# mm_legend_v2.net
KiCad netlist of a schematic drawn in EAGLE
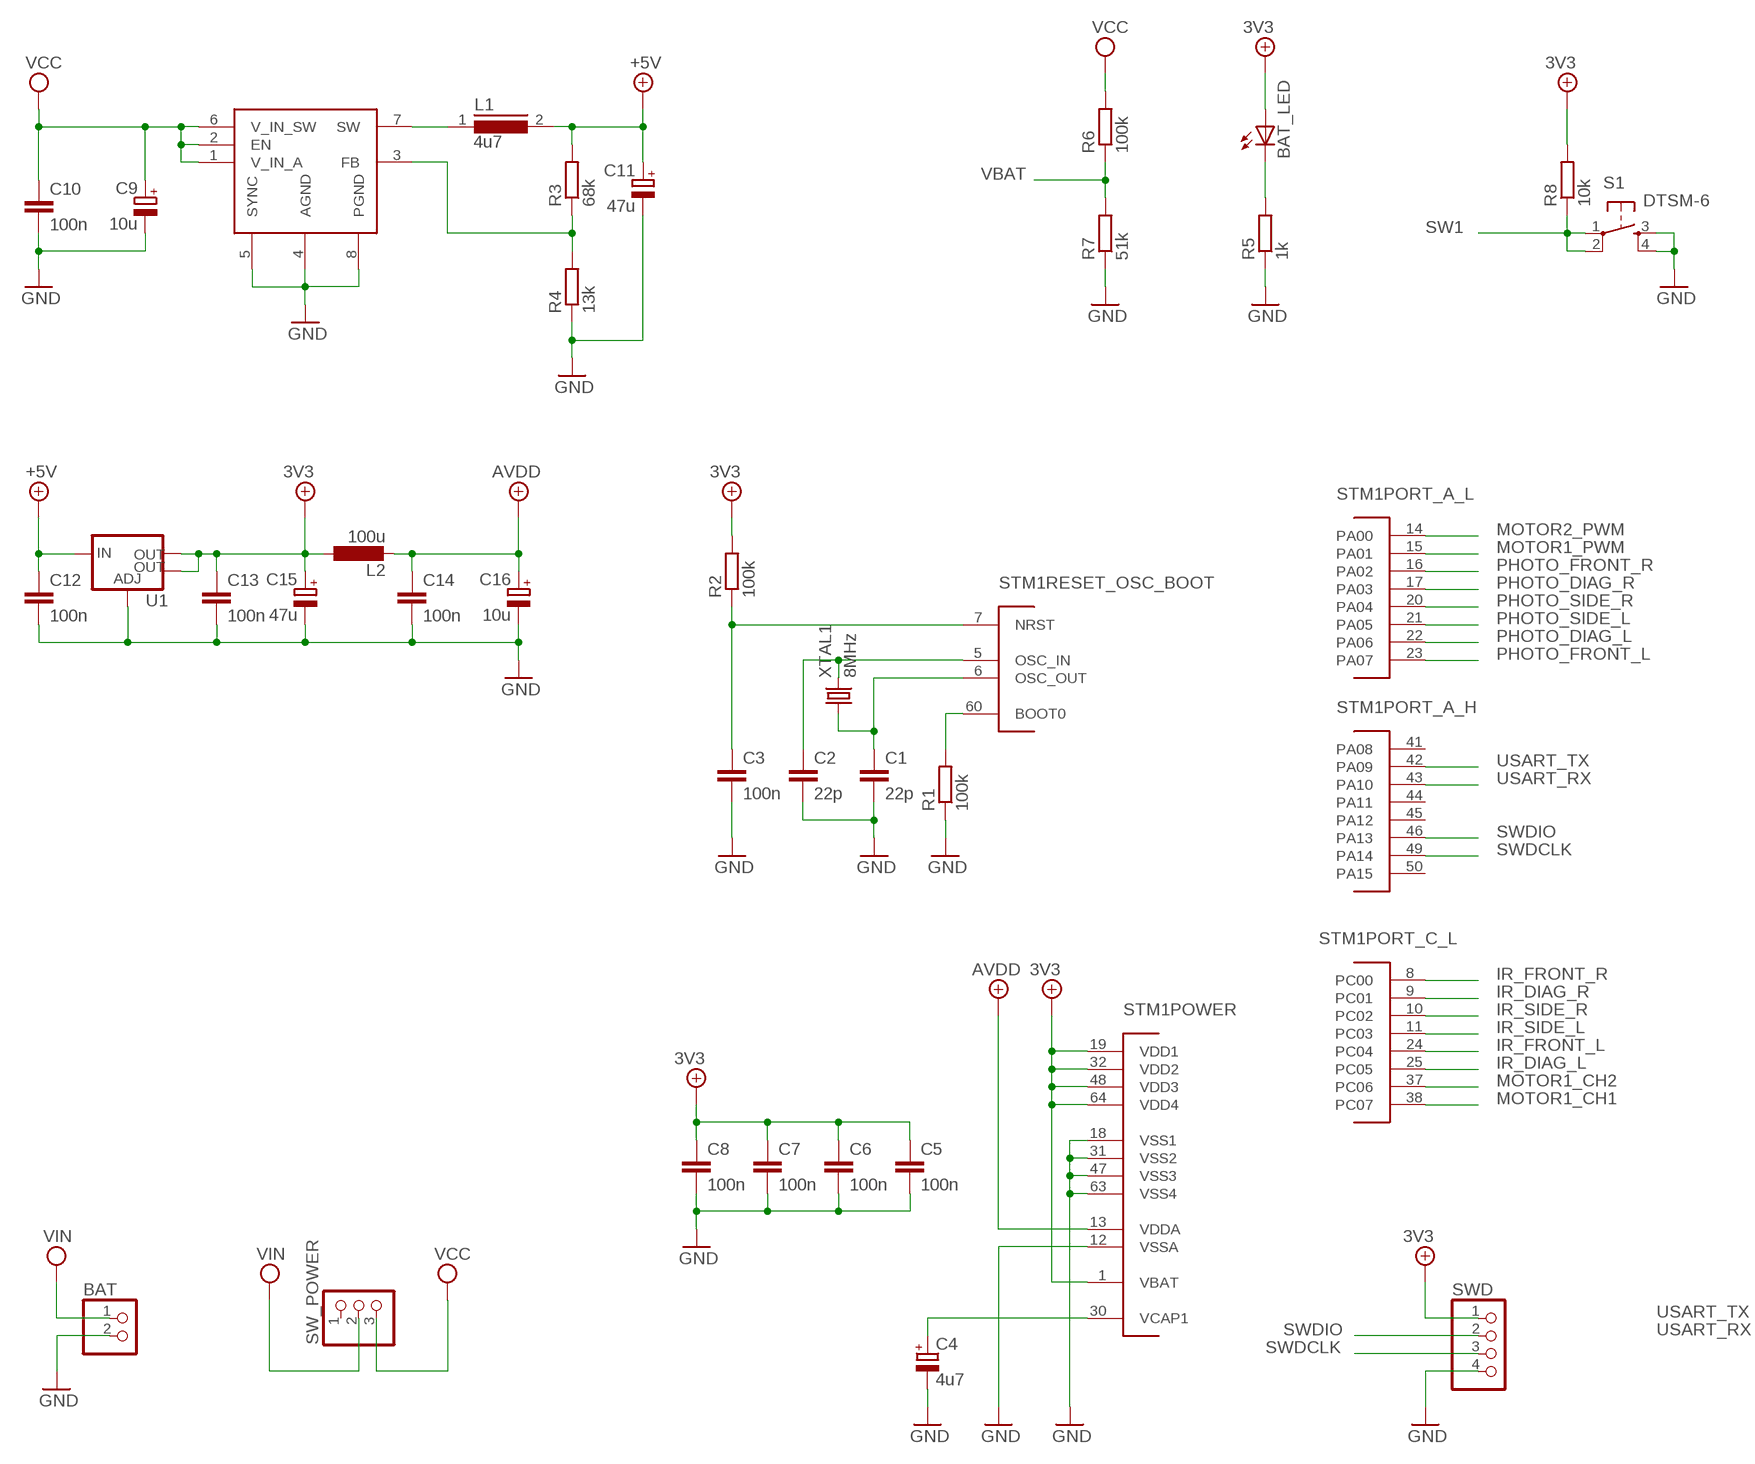
[diagram p0: schematic, sheet 1, part 1 of 2]
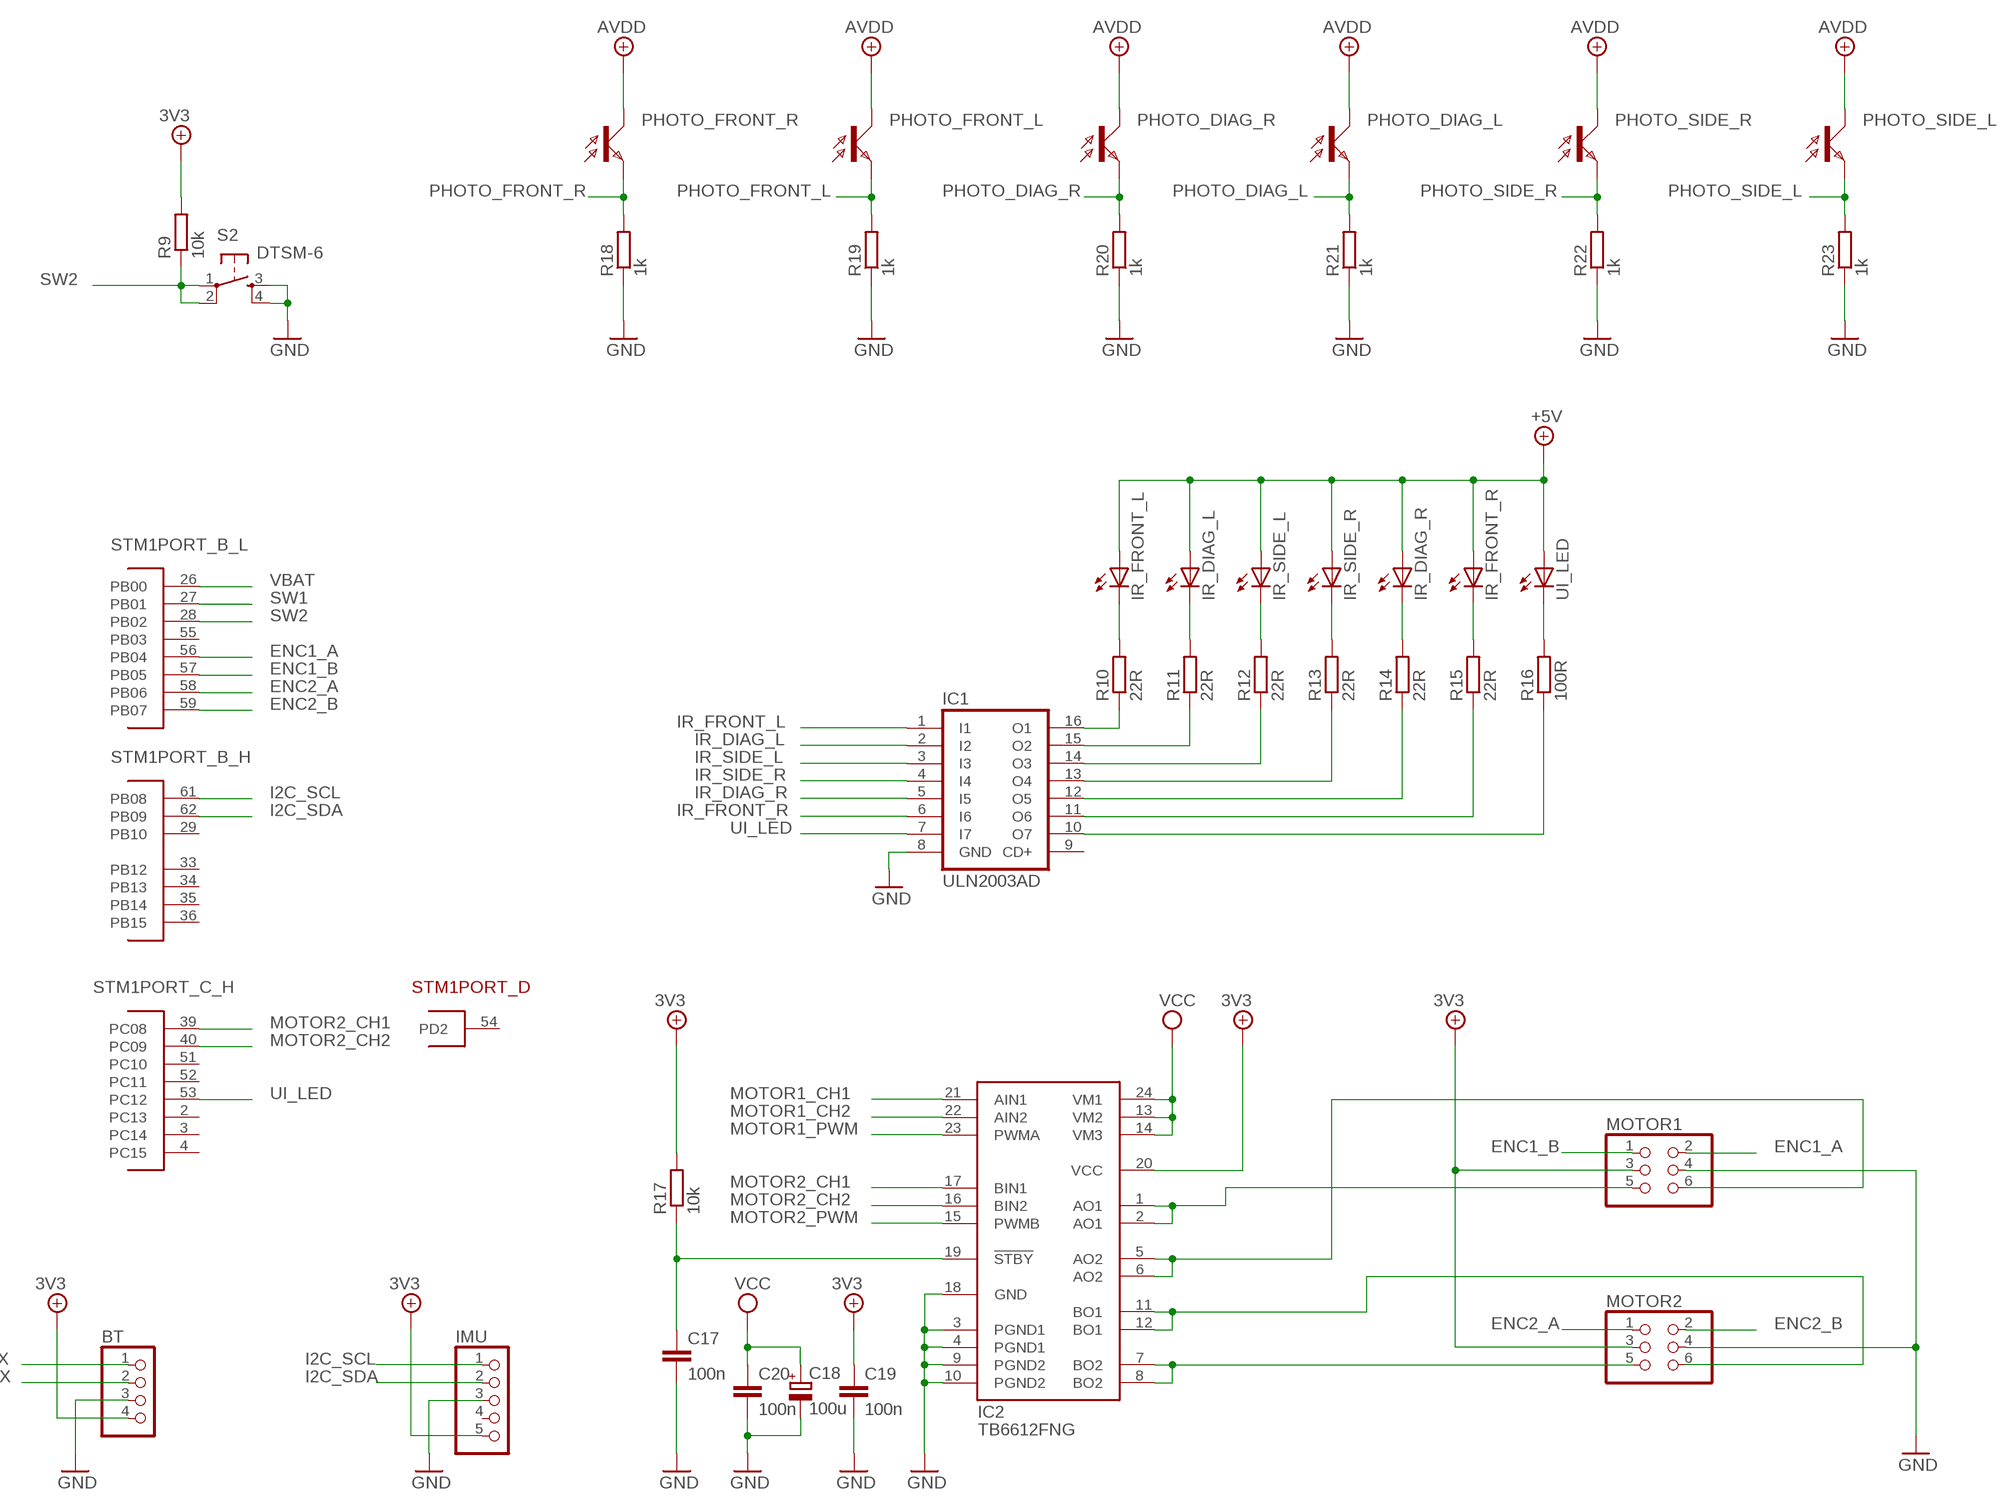
[diagram p1: schematic, sheet 1, part 2 of 2]

(export (version "E")
  (design (tool "Eeschema 10.0.6"))
  (components
    (comp (ref "BAT")
      (value "PINHD-1X2")
      (footprint "eagle-import:1X02")
      (libsource (lib "eagle-import") (part "PINHD-1X2"))
    )
    (comp (ref "BAT_LED")
      (value "LEDCHIP-LED0805")
      (footprint "eagle-import:CHIP-LED0805")
      (libsource (lib "eagle-import") (part "LEDCHIP-LED0805"))
    )
    (comp (ref "BT")
      (value "PINHD-1X4")
      (footprint "eagle-import:1X04")
      (libsource (lib "eagle-import") (part "PINHD-1X4"))
    )
    (comp (ref "C1")
      (value "22p")
      (footprint "eagle-import:C0805K")
      (libsource (lib "eagle-import") (part "C-EUC0805K"))
    )
    (comp (ref "C2")
      (value "22p")
      (footprint "eagle-import:C0805K")
      (libsource (lib "eagle-import") (part "C-EUC0805K"))
    )
    (comp (ref "C3")
      (value "100n")
      (footprint "eagle-import:C0805K")
      (libsource (lib "eagle-import") (part "C-EUC0805K"))
    )
    (comp (ref "C4")
      (value "4u7")
      (footprint "eagle-import:A_3216-18R")
      (libsource (lib "eagle-import") (part "CPOL-EUA/3216-18R"))
    )
    (comp (ref "C5")
      (value "100n")
      (footprint "eagle-import:C0805K")
      (libsource (lib "eagle-import") (part "C-EUC0805K"))
    )
    (comp (ref "C6")
      (value "100n")
      (footprint "eagle-import:C0805K")
      (libsource (lib "eagle-import") (part "C-EUC0805K"))
    )
    (comp (ref "C7")
      (value "100n")
      (footprint "eagle-import:C0805K")
      (libsource (lib "eagle-import") (part "C-EUC0805K"))
    )
    (comp (ref "C8")
      (value "100n")
      (footprint "eagle-import:C0805K")
      (libsource (lib "eagle-import") (part "C-EUC0805K"))
    )
    (comp (ref "C9")
      (value "10u")
      (footprint "eagle-import:A_3216-18R")
      (libsource (lib "eagle-import") (part "CPOL-EUA/3216-18R"))
    )
    (comp (ref "C10")
      (value "100n")
      (footprint "eagle-import:C0805K")
      (libsource (lib "eagle-import") (part "C-EUC0805K"))
    )
    (comp (ref "C11")
      (value "47u")
      (footprint "eagle-import:B_3528-21W")
      (libsource (lib "eagle-import") (part "CPOL-EUB/3528-21W"))
    )
    (comp (ref "C12")
      (value "100n")
      (footprint "eagle-import:C0805K")
      (libsource (lib "eagle-import") (part "C-EUC0805K"))
    )
    (comp (ref "C13")
      (value "100n")
      (footprint "eagle-import:C0805K")
      (libsource (lib "eagle-import") (part "C-EUC0805K"))
    )
    (comp (ref "C14")
      (value "100n")
      (footprint "eagle-import:C0805K")
      (libsource (lib "eagle-import") (part "C-EUC0805K"))
    )
    (comp (ref "C15")
      (value "47u")
      (footprint "eagle-import:B_3528-21W")
      (libsource (lib "eagle-import") (part "CPOL-EUB/3528-21W"))
    )
    (comp (ref "C16")
      (value "10u")
      (footprint "eagle-import:A_3216-18R")
      (libsource (lib "eagle-import") (part "CPOL-EUA/3216-18R"))
    )
    (comp (ref "C17")
      (value "100n")
      (footprint "eagle-import:C0805K")
      (libsource (lib "eagle-import") (part "C-EUC0805K"))
    )
    (comp (ref "C18")
      (value "100u")
      (footprint "eagle-import:C_6032-28R")
      (libsource (lib "eagle-import") (part "CPOL-EUC/6032-28R"))
    )
    (comp (ref "C19")
      (value "100n")
      (footprint "eagle-import:C0805K")
      (libsource (lib "eagle-import") (part "C-EUC0805K"))
    )
    (comp (ref "C20")
      (value "100n")
      (footprint "eagle-import:C0805K")
      (libsource (lib "eagle-import") (part "C-EUC0805K"))
    )
    (comp (ref "IC1")
      (value "ULN2003AD")
      (footprint "eagle-import:SO16")
      (libsource (lib "eagle-import") (part "ULN2003AD"))
    )
    (comp (ref "IC2")
      (value "TB6612FNG")
      (footprint "eagle-import:SSOP24")
      (libsource (lib "eagle-import") (part "TB6612FNG"))
    )
    (comp (ref "IMU")
      (value "PINHD-1X5")
      (footprint "eagle-import:1X05")
      (libsource (lib "eagle-import") (part "PINHD-1X5"))
    )
    (comp (ref "IR_DIAG_L")
      (value "LED5MM")
      (footprint "eagle-import:LED5MM")
      (libsource (lib "eagle-import") (part "LED5MM"))
    )
    (comp (ref "IR_DIAG_R")
      (value "LED5MM")
      (footprint "eagle-import:LED5MM")
      (libsource (lib "eagle-import") (part "LED5MM"))
    )
    (comp (ref "IR_FRONT_L")
      (value "LED5MM")
      (footprint "eagle-import:LED5MM")
      (libsource (lib "eagle-import") (part "LED5MM"))
    )
    (comp (ref "IR_FRONT_R")
      (value "LED5MM")
      (footprint "eagle-import:LED5MM")
      (libsource (lib "eagle-import") (part "LED5MM"))
    )
    (comp (ref "IR_SIDE_L")
      (value "LED5MM")
      (footprint "eagle-import:LED5MM")
      (libsource (lib "eagle-import") (part "LED5MM"))
    )
    (comp (ref "IR_SIDE_R")
      (value "LED5MM")
      (footprint "eagle-import:LED5MM")
      (libsource (lib "eagle-import") (part "LED5MM"))
    )
    (comp (ref "L1")
      (value "4u7")
      (footprint "eagle-import:DR74")
      (libsource (lib "eagle-import") (part "DR74"))
    )
    (comp (ref "L2")
      (value "100u")
      (footprint "eagle-import:L1812")
      (libsource (lib "eagle-import") (part "L-EUL1812"))
    )
    (comp (ref "MOTOR1")
      (value "PINHD-2X3")
      (footprint "eagle-import:2X03")
      (libsource (lib "eagle-import") (part "PINHD-2X3"))
    )
    (comp (ref "MOTOR2")
      (value "PINHD-2X3")
      (footprint "eagle-import:2X03")
      (libsource (lib "eagle-import") (part "PINHD-2X3"))
    )
    (comp (ref "PHOTO_DIAG_L")
      (value "PHOTO_TRANSISTOR_5MM")
      (footprint "eagle-import:5MM")
      (libsource (lib "eagle-import") (part "PHOTO_TRANSISTOR_5MM"))
    )
    (comp (ref "PHOTO_DIAG_R")
      (value "PHOTO_TRANSISTOR_5MM")
      (footprint "eagle-import:5MM")
      (libsource (lib "eagle-import") (part "PHOTO_TRANSISTOR_5MM"))
    )
    (comp (ref "PHOTO_FRONT_L")
      (value "PHOTO_TRANSISTOR_5MM")
      (footprint "eagle-import:5MM")
      (libsource (lib "eagle-import") (part "PHOTO_TRANSISTOR_5MM"))
    )
    (comp (ref "PHOTO_FRONT_R")
      (value "PHOTO_TRANSISTOR_5MM")
      (footprint "eagle-import:5MM")
      (libsource (lib "eagle-import") (part "PHOTO_TRANSISTOR_5MM"))
    )
    (comp (ref "PHOTO_SIDE_L")
      (value "PHOTO_TRANSISTOR_5MM")
      (footprint "eagle-import:5MM")
      (libsource (lib "eagle-import") (part "PHOTO_TRANSISTOR_5MM"))
    )
    (comp (ref "PHOTO_SIDE_R")
      (value "PHOTO_TRANSISTOR_5MM")
      (footprint "eagle-import:5MM")
      (libsource (lib "eagle-import") (part "PHOTO_TRANSISTOR_5MM"))
    )
    (comp (ref "R1")
      (value "100k")
      (footprint "eagle-import:R0805W")
      (libsource (lib "eagle-import") (part "R-EU_R0805W"))
    )
    (comp (ref "R2")
      (value "100k")
      (footprint "eagle-import:R0805W")
      (libsource (lib "eagle-import") (part "R-EU_R0805W"))
    )
    (comp (ref "R3")
      (value "68k")
      (footprint "eagle-import:R0805W")
      (libsource (lib "eagle-import") (part "R-EU_R0805W"))
    )
    (comp (ref "R4")
      (value "13k")
      (footprint "eagle-import:R0805W")
      (libsource (lib "eagle-import") (part "R-EU_R0805W"))
    )
    (comp (ref "R5")
      (value "1k")
      (footprint "eagle-import:R0805W")
      (libsource (lib "eagle-import") (part "R-EU_R0805W"))
    )
    (comp (ref "R6")
      (value "100k")
      (footprint "eagle-import:R0805W")
      (libsource (lib "eagle-import") (part "R-EU_R0805W"))
    )
    (comp (ref "R7")
      (value "51k")
      (footprint "eagle-import:R0805W")
      (libsource (lib "eagle-import") (part "R-EU_R0805W"))
    )
    (comp (ref "R8")
      (value "10k")
      (footprint "eagle-import:R0805W")
      (libsource (lib "eagle-import") (part "R-EU_R0805W"))
    )
    (comp (ref "R9")
      (value "10k")
      (footprint "eagle-import:R0805W")
      (libsource (lib "eagle-import") (part "R-EU_R0805W"))
    )
    (comp (ref "R10")
      (value "22R")
      (footprint "eagle-import:R0805W")
      (libsource (lib "eagle-import") (part "R-EU_R0805W"))
    )
    (comp (ref "R11")
      (value "22R")
      (footprint "eagle-import:R0805W")
      (libsource (lib "eagle-import") (part "R-EU_R0805W"))
    )
    (comp (ref "R12")
      (value "22R")
      (footprint "eagle-import:R0805W")
      (libsource (lib "eagle-import") (part "R-EU_R0805W"))
    )
    (comp (ref "R13")
      (value "22R")
      (footprint "eagle-import:R0805W")
      (libsource (lib "eagle-import") (part "R-EU_R0805W"))
    )
    (comp (ref "R14")
      (value "22R")
      (footprint "eagle-import:R0805W")
      (libsource (lib "eagle-import") (part "R-EU_R0805W"))
    )
    (comp (ref "R15")
      (value "22R")
      (footprint "eagle-import:R0805W")
      (libsource (lib "eagle-import") (part "R-EU_R0805W"))
    )
    (comp (ref "R16")
      (value "100R")
      (footprint "eagle-import:R0805W")
      (libsource (lib "eagle-import") (part "R-EU_R0805W"))
    )
    (comp (ref "R17")
      (value "10k")
      (footprint "eagle-import:R0805W")
      (libsource (lib "eagle-import") (part "R-EU_R0805W"))
    )
    (comp (ref "R18")
      (value "1k")
      (footprint "eagle-import:R0805W")
      (libsource (lib "eagle-import") (part "R-EU_R0805W"))
    )
    (comp (ref "R19")
      (value "1k")
      (footprint "eagle-import:R0805W")
      (libsource (lib "eagle-import") (part "R-EU_R0805W"))
    )
    (comp (ref "R20")
      (value "1k")
      (footprint "eagle-import:R0805W")
      (libsource (lib "eagle-import") (part "R-EU_R0805W"))
    )
    (comp (ref "R21")
      (value "1k")
      (footprint "eagle-import:R0805W")
      (libsource (lib "eagle-import") (part "R-EU_R0805W"))
    )
    (comp (ref "R22")
      (value "1k")
      (footprint "eagle-import:R0805W")
      (libsource (lib "eagle-import") (part "R-EU_R0805W"))
    )
    (comp (ref "R23")
      (value "1k")
      (footprint "eagle-import:R0805W")
      (libsource (lib "eagle-import") (part "R-EU_R0805W"))
    )
    (comp (ref "S1")
      (value "DTSM-6")
      (footprint "eagle-import:DTSM-6")
      (libsource (lib "eagle-import") (part "DTSM-6"))
    )
    (comp (ref "S2")
      (value "DTSM-6")
      (footprint "eagle-import:DTSM-6")
      (libsource (lib "eagle-import") (part "DTSM-6"))
    )
    (comp (ref "STM1")
      (value "STM32F401RB")
      (footprint "eagle-import:LQFP64")
      (libsource (lib "eagle-import") (part "STM32F401RB"))
    )
    (comp (ref "SWD")
      (value "PINHD-1X4")
      (footprint "eagle-import:1X04")
      (libsource (lib "eagle-import") (part "PINHD-1X4"))
    )
    (comp (ref "SW_POWER")
      (value "PINHD-1X3")
      (footprint "eagle-import:1X03")
      (libsource (lib "eagle-import") (part "PINHD-1X3"))
    )
    (comp (ref "U$2")
      (value "ST1S10PHR")
      (footprint "eagle-import:SO8")
      (libsource (lib "eagle-import") (part "ST1S10PHR"))
    )
    (comp (ref "U1")
      (value "V_REG_LM1117SOT223")
      (footprint "eagle-import:SOT223")
      (libsource (lib "eagle-import") (part "V_REG_LM1117SOT223"))
    )
    (comp (ref "UI_LED")
      (value "LEDCHIP-LED0805")
      (footprint "eagle-import:CHIP-LED0805")
      (libsource (lib "eagle-import") (part "LEDCHIP-LED0805"))
    )
    (comp (ref "XTAL1")
      (value "8MHz")
      (footprint "eagle-import:SMD_50X32")
      (libsource (lib "eagle-import") (part "XTAL_SMD_50X32"))
    )
  )
  (nets
    (net (code "1") (name "+5V") (class "Default")
      (node (ref "C11") (pin "+") (pinfunction "+_+") (pintype "passive"))
      (node (ref "C12") (pin "1") (pinfunction "1_1") (pintype "passive"))
      (node (ref "IR_DIAG_L") (pin "A") (pinfunction "A_A") (pintype "passive"))
      (node (ref "IR_DIAG_R") (pin "A") (pinfunction "A_A") (pintype "passive"))
      (node (ref "IR_FRONT_L") (pin "A") (pinfunction "A_A") (pintype "passive"))
      (node (ref "IR_FRONT_R") (pin "A") (pinfunction "A_A") (pintype "passive"))
      (node (ref "IR_SIDE_L") (pin "A") (pinfunction "A_A") (pintype "passive"))
      (node (ref "IR_SIDE_R") (pin "A") (pinfunction "A_A") (pintype "passive"))
      (node (ref "L1") (pin "2") (pinfunction "2_2") (pintype "passive"))
      (node (ref "R3") (pin "2") (pinfunction "2_2") (pintype "passive"))
      (node (ref "U1") (pin "3") (pinfunction "IN_3") (pintype "input"))
      (node (ref "UI_LED") (pin "A") (pinfunction "A_A") (pintype "passive"))
    )
    (net (code "2") (name "/ENC1_A") (class "Default")
      (node (ref "MOTOR1") (pin "2") (pinfunction "2_2") (pintype "passive"))
      (node (ref "STM1") (pin "56") (pinfunction "PB04_56") (pintype "bidirectional"))
    )
    (net (code "3") (name "/ENC1_B") (class "Default")
      (node (ref "MOTOR1") (pin "1") (pinfunction "1_1") (pintype "passive"))
      (node (ref "STM1") (pin "57") (pinfunction "PB05_57") (pintype "bidirectional"))
    )
    (net (code "4") (name "/ENC2_A") (class "Default")
      (node (ref "MOTOR2") (pin "1") (pinfunction "1_1") (pintype "passive"))
      (node (ref "STM1") (pin "58") (pinfunction "PB06_58") (pintype "bidirectional"))
    )
    (net (code "5") (name "/ENC2_B") (class "Default")
      (node (ref "MOTOR2") (pin "2") (pinfunction "2_2") (pintype "passive"))
      (node (ref "STM1") (pin "59") (pinfunction "PB07_59") (pintype "bidirectional"))
    )
    (net (code "6") (name "/I2C_SCL") (class "Default")
      (node (ref "IMU") (pin "1") (pinfunction "1_1") (pintype "passive"))
      (node (ref "STM1") (pin "61") (pinfunction "PB08_61") (pintype "bidirectional"))
    )
    (net (code "7") (name "/I2C_SDA") (class "Default")
      (node (ref "IMU") (pin "2") (pinfunction "2_2") (pintype "passive"))
      (node (ref "STM1") (pin "62") (pinfunction "PB09_62") (pintype "bidirectional"))
    )
    (net (code "8") (name "/IR_DIAG_L") (class "Default")
      (node (ref "IC1") (pin "2") (pinfunction "I2_2") (pintype "input"))
      (node (ref "STM1") (pin "25") (pinfunction "PC05_25") (pintype "bidirectional"))
    )
    (net (code "9") (name "/IR_DIAG_R") (class "Default")
      (node (ref "IC1") (pin "5") (pinfunction "I5_5") (pintype "input"))
      (node (ref "STM1") (pin "9") (pinfunction "PC01_9") (pintype "bidirectional"))
    )
    (net (code "10") (name "/IR_FRONT_L") (class "Default")
      (node (ref "IC1") (pin "1") (pinfunction "I1_1") (pintype "input"))
      (node (ref "STM1") (pin "24") (pinfunction "PC04_24") (pintype "bidirectional"))
    )
    (net (code "11") (name "/IR_FRONT_R") (class "Default")
      (node (ref "IC1") (pin "6") (pinfunction "I6_6") (pintype "input"))
      (node (ref "STM1") (pin "8") (pinfunction "PC00_8") (pintype "bidirectional"))
    )
    (net (code "12") (name "/IR_SIDE_L") (class "Default")
      (node (ref "IC1") (pin "3") (pinfunction "I3_3") (pintype "input"))
      (node (ref "STM1") (pin "11") (pinfunction "PC03_11") (pintype "bidirectional"))
    )
    (net (code "13") (name "/IR_SIDE_R") (class "Default")
      (node (ref "IC1") (pin "4") (pinfunction "I4_4") (pintype "input"))
      (node (ref "STM1") (pin "10") (pinfunction "PC02_10") (pintype "bidirectional"))
    )
    (net (code "14") (name "/MOTOR1_CH1") (class "Default")
      (node (ref "IC2") (pin "21") (pinfunction "AIN1_21") (pintype "bidirectional"))
      (node (ref "STM1") (pin "38") (pinfunction "PC07_38") (pintype "bidirectional"))
    )
    (net (code "15") (name "/MOTOR1_CH2") (class "Default")
      (node (ref "IC2") (pin "22") (pinfunction "AIN2_22") (pintype "bidirectional"))
      (node (ref "STM1") (pin "37") (pinfunction "PC06_37") (pintype "bidirectional"))
    )
    (net (code "16") (name "/MOTOR1_PWM") (class "Default")
      (node (ref "IC2") (pin "23") (pinfunction "PWMA_23") (pintype "bidirectional"))
      (node (ref "STM1") (pin "15") (pinfunction "PA01_15") (pintype "bidirectional"))
    )
    (net (code "17") (name "/MOTOR2_CH1") (class "Default")
      (node (ref "IC2") (pin "17") (pinfunction "BIN1_17") (pintype "bidirectional"))
      (node (ref "STM1") (pin "39") (pinfunction "PC08_39") (pintype "bidirectional"))
    )
    (net (code "18") (name "/MOTOR2_CH2") (class "Default")
      (node (ref "IC2") (pin "16") (pinfunction "BIN2_16") (pintype "bidirectional"))
      (node (ref "STM1") (pin "40") (pinfunction "PC09_40") (pintype "bidirectional"))
    )
    (net (code "19") (name "/MOTOR2_PWM") (class "Default")
      (node (ref "IC2") (pin "15") (pinfunction "PWMB_15") (pintype "bidirectional"))
      (node (ref "STM1") (pin "14") (pinfunction "PA00_14") (pintype "bidirectional"))
    )
    (net (code "20") (name "/PHOTO_DIAG_L") (class "Default")
      (node (ref "PHOTO_DIAG_L") (pin "E") (pinfunction "E_E") (pintype "passive"))
      (node (ref "R21") (pin "2") (pinfunction "2_2") (pintype "passive"))
      (node (ref "STM1") (pin "22") (pinfunction "PA06_22") (pintype "bidirectional"))
    )
    (net (code "21") (name "/PHOTO_DIAG_R") (class "Default")
      (node (ref "PHOTO_DIAG_R") (pin "E") (pinfunction "E_E") (pintype "passive"))
      (node (ref "R20") (pin "2") (pinfunction "2_2") (pintype "passive"))
      (node (ref "STM1") (pin "17") (pinfunction "PA03_17") (pintype "bidirectional"))
    )
    (net (code "22") (name "/PHOTO_FRONT_L") (class "Default")
      (node (ref "PHOTO_FRONT_L") (pin "E") (pinfunction "E_E") (pintype "passive"))
      (node (ref "R19") (pin "2") (pinfunction "2_2") (pintype "passive"))
      (node (ref "STM1") (pin "23") (pinfunction "PA07_23") (pintype "bidirectional"))
    )
    (net (code "23") (name "/PHOTO_FRONT_R") (class "Default")
      (node (ref "PHOTO_FRONT_R") (pin "E") (pinfunction "E_E") (pintype "passive"))
      (node (ref "R18") (pin "2") (pinfunction "2_2") (pintype "passive"))
      (node (ref "STM1") (pin "16") (pinfunction "PA02_16") (pintype "bidirectional"))
    )
    (net (code "24") (name "/PHOTO_SIDE_L") (class "Default")
      (node (ref "PHOTO_SIDE_L") (pin "E") (pinfunction "E_E") (pintype "passive"))
      (node (ref "R23") (pin "2") (pinfunction "2_2") (pintype "passive"))
      (node (ref "STM1") (pin "21") (pinfunction "PA05_21") (pintype "bidirectional"))
    )
    (net (code "25") (name "/PHOTO_SIDE_R") (class "Default")
      (node (ref "PHOTO_SIDE_R") (pin "E") (pinfunction "E_E") (pintype "passive"))
      (node (ref "R22") (pin "2") (pinfunction "2_2") (pintype "passive"))
      (node (ref "STM1") (pin "20") (pinfunction "PA04_20") (pintype "bidirectional"))
    )
    (net (code "26") (name "/SW1") (class "Default")
      (node (ref "R8") (pin "1") (pinfunction "1_1") (pintype "passive"))
      (node (ref "S1") (pin "1") (pinfunction "1_1") (pintype "passive"))
      (node (ref "S1") (pin "2") (pinfunction "2_2") (pintype "passive"))
      (node (ref "STM1") (pin "27") (pinfunction "PB01_27") (pintype "bidirectional"))
    )
    (net (code "27") (name "/SW2") (class "Default")
      (node (ref "R9") (pin "1") (pinfunction "1_1") (pintype "passive"))
      (node (ref "S2") (pin "1") (pinfunction "1_1") (pintype "passive"))
      (node (ref "S2") (pin "2") (pinfunction "2_2") (pintype "passive"))
      (node (ref "STM1") (pin "28") (pinfunction "PB02_28") (pintype "bidirectional"))
    )
    (net (code "28") (name "/SWDCLK") (class "Default")
      (node (ref "STM1") (pin "49") (pinfunction "PA14_49") (pintype "bidirectional"))
      (node (ref "SWD") (pin "3") (pinfunction "3_3") (pintype "passive"))
    )
    (net (code "29") (name "/SWDIO") (class "Default")
      (node (ref "STM1") (pin "46") (pinfunction "PA13_46") (pintype "bidirectional"))
      (node (ref "SWD") (pin "2") (pinfunction "2_2") (pintype "passive"))
    )
    (net (code "30") (name "/UI_LED") (class "Default")
      (node (ref "IC1") (pin "7") (pinfunction "I7_7") (pintype "input"))
      (node (ref "STM1") (pin "53") (pinfunction "PC12_53") (pintype "bidirectional"))
    )
    (net (code "31") (name "/USART_RX") (class "Default")
      (node (ref "BT") (pin "2") (pinfunction "2_2") (pintype "passive"))
      (node (ref "STM1") (pin "43") (pinfunction "PA10_43") (pintype "bidirectional"))
    )
    (net (code "32") (name "/USART_TX") (class "Default")
      (node (ref "BT") (pin "1") (pinfunction "1_1") (pintype "passive"))
      (node (ref "STM1") (pin "42") (pinfunction "PA09_42") (pintype "bidirectional"))
    )
    (net (code "33") (name "/VBAT") (class "Default")
      (node (ref "R6") (pin "1") (pinfunction "1_1") (pintype "passive"))
      (node (ref "R7") (pin "2") (pinfunction "2_2") (pintype "passive"))
      (node (ref "STM1") (pin "26") (pinfunction "PB00_26") (pintype "bidirectional"))
    )
    (net (code "34") (name "3V3") (class "Default")
      (node (ref "BAT_LED") (pin "A") (pinfunction "A_A") (pintype "passive"))
      (node (ref "BT") (pin "4") (pinfunction "4_4") (pintype "passive"))
      (node (ref "C13") (pin "1") (pinfunction "1_1") (pintype "passive"))
      (node (ref "C15") (pin "+") (pinfunction "+_+") (pintype "passive"))
      (node (ref "C19") (pin "1") (pinfunction "1_1") (pintype "passive"))
      (node (ref "C5") (pin "1") (pinfunction "1_1") (pintype "passive"))
      (node (ref "C6") (pin "1") (pinfunction "1_1") (pintype "passive"))
      (node (ref "C7") (pin "1") (pinfunction "1_1") (pintype "passive"))
      (node (ref "C8") (pin "1") (pinfunction "1_1") (pintype "passive"))
      (node (ref "IC2") (pin "20") (pinfunction "VCC_20") (pintype "bidirectional"))
      (node (ref "IMU") (pin "5") (pinfunction "5_5") (pintype "passive"))
      (node (ref "L2") (pin "1") (pinfunction "1_1") (pintype "passive"))
      (node (ref "MOTOR1") (pin "3") (pinfunction "3_3") (pintype "passive"))
      (node (ref "MOTOR2") (pin "3") (pinfunction "3_3") (pintype "passive"))
      (node (ref "R17") (pin "2") (pinfunction "2_2") (pintype "passive"))
      (node (ref "R2") (pin "2") (pinfunction "2_2") (pintype "passive"))
      (node (ref "R8") (pin "2") (pinfunction "2_2") (pintype "passive"))
      (node (ref "R9") (pin "2") (pinfunction "2_2") (pintype "passive"))
      (node (ref "STM1") (pin "1") (pinfunction "VBAT_1") (pintype "bidirectional"))
      (node (ref "STM1") (pin "19") (pinfunction "VDD1_19") (pintype "bidirectional"))
      (node (ref "STM1") (pin "32") (pinfunction "VDD2_32") (pintype "bidirectional"))
      (node (ref "STM1") (pin "48") (pinfunction "VDD3_48") (pintype "bidirectional"))
      (node (ref "STM1") (pin "64") (pinfunction "VDD4_64") (pintype "bidirectional"))
      (node (ref "SWD") (pin "1") (pinfunction "1_1") (pintype "passive"))
      (node (ref "U1") (pin "2") (pinfunction "OUT_2") (pintype "output"))
      (node (ref "U1") (pin "4") (pinfunction "OUT_4") (pintype "output"))
    )
    (net (code "35") (name "AVDD") (class "Default")
      (node (ref "C14") (pin "1") (pinfunction "1_1") (pintype "passive"))
      (node (ref "C16") (pin "+") (pinfunction "+_+") (pintype "passive"))
      (node (ref "L2") (pin "2") (pinfunction "2_2") (pintype "passive"))
      (node (ref "PHOTO_DIAG_L") (pin "C") (pinfunction "C_C") (pintype "passive"))
      (node (ref "PHOTO_DIAG_R") (pin "C") (pinfunction "C_C") (pintype "passive"))
      (node (ref "PHOTO_FRONT_L") (pin "C") (pinfunction "C_C") (pintype "passive"))
      (node (ref "PHOTO_FRONT_R") (pin "C") (pinfunction "C_C") (pintype "passive"))
      (node (ref "PHOTO_SIDE_L") (pin "C") (pinfunction "C_C") (pintype "passive"))
      (node (ref "PHOTO_SIDE_R") (pin "C") (pinfunction "C_C") (pintype "passive"))
      (node (ref "STM1") (pin "13") (pinfunction "VDDA_13") (pintype "bidirectional"))
    )
    (net (code "36") (name "GND") (class "Default")
      (node (ref "BAT") (pin "2") (pinfunction "2_2") (pintype "passive"))
      (node (ref "BT") (pin "3") (pinfunction "3_3") (pintype "passive"))
      (node (ref "C1") (pin "2") (pinfunction "2_2") (pintype "passive"))
      (node (ref "C10") (pin "2") (pinfunction "2_2") (pintype "passive"))
      (node (ref "C11") (pin "-") (pinfunction "-_-") (pintype "passive"))
      (node (ref "C12") (pin "2") (pinfunction "2_2") (pintype "passive"))
      (node (ref "C13") (pin "2") (pinfunction "2_2") (pintype "passive"))
      (node (ref "C14") (pin "2") (pinfunction "2_2") (pintype "passive"))
      (node (ref "C15") (pin "-") (pinfunction "-_-") (pintype "passive"))
      (node (ref "C16") (pin "-") (pinfunction "-_-") (pintype "passive"))
      (node (ref "C17") (pin "2") (pinfunction "2_2") (pintype "passive"))
      (node (ref "C18") (pin "-") (pinfunction "-_-") (pintype "passive"))
      (node (ref "C19") (pin "2") (pinfunction "2_2") (pintype "passive"))
      (node (ref "C2") (pin "2") (pinfunction "2_2") (pintype "passive"))
      (node (ref "C20") (pin "2") (pinfunction "2_2") (pintype "passive"))
      (node (ref "C3") (pin "2") (pinfunction "2_2") (pintype "passive"))
      (node (ref "C4") (pin "-") (pinfunction "-_-") (pintype "passive"))
      (node (ref "C5") (pin "2") (pinfunction "2_2") (pintype "passive"))
      (node (ref "C6") (pin "2") (pinfunction "2_2") (pintype "passive"))
      (node (ref "C7") (pin "2") (pinfunction "2_2") (pintype "passive"))
      (node (ref "C8") (pin "2") (pinfunction "2_2") (pintype "passive"))
      (node (ref "C9") (pin "-") (pinfunction "-_-") (pintype "passive"))
      (node (ref "IC1") (pin "8") (pinfunction "GND_8") (pintype "power_in"))
      (node (ref "IC2") (pin "10") (pinfunction "PGND2_10") (pintype "bidirectional"))
      (node (ref "IC2") (pin "18") (pinfunction "GND_18") (pintype "bidirectional"))
      (node (ref "IC2") (pin "3") (pinfunction "PGND1_3") (pintype "bidirectional"))
      (node (ref "IC2") (pin "4") (pinfunction "PGND1_4") (pintype "bidirectional"))
      (node (ref "IC2") (pin "9") (pinfunction "PGND2_9") (pintype "bidirectional"))
      (node (ref "IMU") (pin "3") (pinfunction "3_3") (pintype "passive"))
      (node (ref "MOTOR1") (pin "4") (pinfunction "4_4") (pintype "passive"))
      (node (ref "MOTOR2") (pin "4") (pinfunction "4_4") (pintype "passive"))
      (node (ref "R1") (pin "1") (pinfunction "1_1") (pintype "passive"))
      (node (ref "R18") (pin "1") (pinfunction "1_1") (pintype "passive"))
      (node (ref "R19") (pin "1") (pinfunction "1_1") (pintype "passive"))
      (node (ref "R20") (pin "1") (pinfunction "1_1") (pintype "passive"))
      (node (ref "R21") (pin "1") (pinfunction "1_1") (pintype "passive"))
      (node (ref "R22") (pin "1") (pinfunction "1_1") (pintype "passive"))
      (node (ref "R23") (pin "1") (pinfunction "1_1") (pintype "passive"))
      (node (ref "R4") (pin "1") (pinfunction "1_1") (pintype "passive"))
      (node (ref "R5") (pin "1") (pinfunction "1_1") (pintype "passive"))
      (node (ref "R7") (pin "1") (pinfunction "1_1") (pintype "passive"))
      (node (ref "S1") (pin "3") (pinfunction "3_3") (pintype "passive"))
      (node (ref "S1") (pin "4") (pinfunction "4_4") (pintype "passive"))
      (node (ref "S2") (pin "3") (pinfunction "3_3") (pintype "passive"))
      (node (ref "S2") (pin "4") (pinfunction "4_4") (pintype "passive"))
      (node (ref "STM1") (pin "12") (pinfunction "VSSA_12") (pintype "bidirectional"))
      (node (ref "STM1") (pin "18") (pinfunction "VSS1_18") (pintype "bidirectional"))
      (node (ref "STM1") (pin "31") (pinfunction "VSS2_31") (pintype "bidirectional"))
      (node (ref "STM1") (pin "47") (pinfunction "VSS3_47") (pintype "bidirectional"))
      (node (ref "STM1") (pin "63") (pinfunction "VSS4_63") (pintype "bidirectional"))
      (node (ref "SWD") (pin "4") (pinfunction "4_4") (pintype "passive"))
      (node (ref "U$2") (pin "4") (pinfunction "AGND_4") (pintype "bidirectional"))
      (node (ref "U$2") (pin "5") (pinfunction "SYNC_5") (pintype "bidirectional"))
      (node (ref "U$2") (pin "8") (pinfunction "PGND_8") (pintype "bidirectional"))
      (node (ref "U1") (pin "1") (pinfunction "ADJ_1") (pintype "input"))
    )
    (net (code "37") (name "Net-(BAT_LED-PadC)") (class "Default")
      (node (ref "BAT_LED") (pin "C") (pinfunction "C_C") (pintype "passive"))
      (node (ref "R5") (pin "2") (pinfunction "2_2") (pintype "passive"))
    )
    (net (code "38") (name "Net-(IC1-O1)") (class "Default")
      (node (ref "IC1") (pin "16") (pinfunction "O1_16") (pintype "open_collector"))
      (node (ref "R10") (pin "1") (pinfunction "1_1") (pintype "passive"))
    )
    (net (code "39") (name "Net-(IC1-O2)") (class "Default")
      (node (ref "IC1") (pin "15") (pinfunction "O2_15") (pintype "open_collector"))
      (node (ref "R11") (pin "1") (pinfunction "1_1") (pintype "passive"))
    )
    (net (code "40") (name "Net-(IC1-O3)") (class "Default")
      (node (ref "IC1") (pin "14") (pinfunction "O3_14") (pintype "open_collector"))
      (node (ref "R12") (pin "1") (pinfunction "1_1") (pintype "passive"))
    )
    (net (code "41") (name "Net-(IC1-O4)") (class "Default")
      (node (ref "IC1") (pin "13") (pinfunction "O4_13") (pintype "open_collector"))
      (node (ref "R13") (pin "1") (pinfunction "1_1") (pintype "passive"))
    )
    (net (code "42") (name "Net-(IC1-O5)") (class "Default")
      (node (ref "IC1") (pin "12") (pinfunction "O5_12") (pintype "open_collector"))
      (node (ref "R14") (pin "1") (pinfunction "1_1") (pintype "passive"))
    )
    (net (code "43") (name "Net-(IC1-O6)") (class "Default")
      (node (ref "IC1") (pin "11") (pinfunction "O6_11") (pintype "open_collector"))
      (node (ref "R15") (pin "1") (pinfunction "1_1") (pintype "passive"))
    )
    (net (code "44") (name "Net-(IC1-O7)") (class "Default")
      (node (ref "IC1") (pin "10") (pinfunction "O7_10") (pintype "open_collector"))
      (node (ref "R16") (pin "1") (pinfunction "1_1") (pintype "passive"))
    )
    (net (code "45") (name "Net-(IC2-AO1-Pad1)") (class "Default")
      (node (ref "IC2") (pin "1") (pinfunction "AO1_1") (pintype "bidirectional"))
      (node (ref "IC2") (pin "2") (pinfunction "AO1_2") (pintype "bidirectional"))
      (node (ref "MOTOR1") (pin "5") (pinfunction "5_5") (pintype "passive"))
    )
    (net (code "46") (name "Net-(IC2-AO2-Pad5)") (class "Default")
      (node (ref "IC2") (pin "5") (pinfunction "AO2_5") (pintype "bidirectional"))
      (node (ref "IC2") (pin "6") (pinfunction "AO2_6") (pintype "bidirectional"))
      (node (ref "MOTOR1") (pin "6") (pinfunction "6_6") (pintype "passive"))
    )
    (net (code "47") (name "Net-(IC2-BO1-Pad11)") (class "Default")
      (node (ref "IC2") (pin "11") (pinfunction "BO1_11") (pintype "bidirectional"))
      (node (ref "IC2") (pin "12") (pinfunction "BO1_12") (pintype "bidirectional"))
      (node (ref "MOTOR2") (pin "6") (pinfunction "6_6") (pintype "passive"))
    )
    (net (code "48") (name "Net-(IC2-BO2-Pad7)") (class "Default")
      (node (ref "IC2") (pin "7") (pinfunction "BO2_7") (pintype "bidirectional"))
      (node (ref "IC2") (pin "8") (pinfunction "BO2_8") (pintype "bidirectional"))
      (node (ref "MOTOR2") (pin "5") (pinfunction "5_5") (pintype "passive"))
    )
    (net (code "49") (name "Net-(IC2-~{STBY})") (class "Default")
      (node (ref "C17") (pin "1") (pinfunction "1_1") (pintype "passive"))
      (node (ref "IC2") (pin "19") (pinfunction "~{STBY}_19") (pintype "bidirectional"))
      (node (ref "R17") (pin "1") (pinfunction "1_1") (pintype "passive"))
    )
    (net (code "50") (name "Net-(IR_DIAG_L-C)") (class "Default")
      (node (ref "IR_DIAG_L") (pin "K") (pinfunction "C_K") (pintype "passive"))
      (node (ref "R11") (pin "2") (pinfunction "2_2") (pintype "passive"))
    )
    (net (code "51") (name "Net-(IR_DIAG_R-C)") (class "Default")
      (node (ref "IR_DIAG_R") (pin "K") (pinfunction "C_K") (pintype "passive"))
      (node (ref "R14") (pin "2") (pinfunction "2_2") (pintype "passive"))
    )
    (net (code "52") (name "Net-(IR_FRONT_L-C)") (class "Default")
      (node (ref "IR_FRONT_L") (pin "K") (pinfunction "C_K") (pintype "passive"))
      (node (ref "R10") (pin "2") (pinfunction "2_2") (pintype "passive"))
    )
    (net (code "53") (name "Net-(IR_FRONT_R-C)") (class "Default")
      (node (ref "IR_FRONT_R") (pin "K") (pinfunction "C_K") (pintype "passive"))
      (node (ref "R15") (pin "2") (pinfunction "2_2") (pintype "passive"))
    )
    (net (code "54") (name "Net-(IR_SIDE_L-C)") (class "Default")
      (node (ref "IR_SIDE_L") (pin "K") (pinfunction "C_K") (pintype "passive"))
      (node (ref "R12") (pin "2") (pinfunction "2_2") (pintype "passive"))
    )
    (net (code "55") (name "Net-(IR_SIDE_R-C)") (class "Default")
      (node (ref "IR_SIDE_R") (pin "K") (pinfunction "C_K") (pintype "passive"))
      (node (ref "R13") (pin "2") (pinfunction "2_2") (pintype "passive"))
    )
    (net (code "56") (name "Net-(R16-Pad2)") (class "Default")
      (node (ref "R16") (pin "2") (pinfunction "2_2") (pintype "passive"))
      (node (ref "UI_LED") (pin "C") (pinfunction "C_C") (pintype "passive"))
    )
    (net (code "57") (name "Net-(STM1H-VCAP1)") (class "Default")
      (node (ref "C4") (pin "+") (pinfunction "+_+") (pintype "passive"))
      (node (ref "STM1") (pin "30") (pinfunction "VCAP1_30") (pintype "bidirectional"))
    )
    (net (code "58") (name "Net-(STM1I-BOOT0)") (class "Default")
      (node (ref "R1") (pin "2") (pinfunction "2_2") (pintype "passive"))
      (node (ref "STM1") (pin "60") (pinfunction "BOOT0_60") (pintype "bidirectional"))
    )
    (net (code "59") (name "Net-(STM1I-NRST)") (class "Default")
      (node (ref "C3") (pin "1") (pinfunction "1_1") (pintype "passive"))
      (node (ref "R2") (pin "1") (pinfunction "1_1") (pintype "passive"))
      (node (ref "STM1") (pin "7") (pinfunction "NRST_7") (pintype "bidirectional"))
    )
    (net (code "60") (name "Net-(STM1I-OSC_IN)") (class "Default")
      (node (ref "C2") (pin "1") (pinfunction "1_1") (pintype "passive"))
      (node (ref "STM1") (pin "5") (pinfunction "OSC_IN_5") (pintype "bidirectional"))
      (node (ref "XTAL1") (pin "2") (pinfunction "2_2") (pintype "passive"))
    )
    (net (code "61") (name "Net-(STM1I-OSC_OUT)") (class "Default")
      (node (ref "C1") (pin "1") (pinfunction "1_1") (pintype "passive"))
      (node (ref "STM1") (pin "6") (pinfunction "OSC_OUT_6") (pintype "bidirectional"))
      (node (ref "XTAL1") (pin "1") (pinfunction "1_1") (pintype "passive"))
    )
    (net (code "62") (name "Net-(U$2-FB)") (class "Default")
      (node (ref "R3") (pin "1") (pinfunction "1_1") (pintype "passive"))
      (node (ref "R4") (pin "2") (pinfunction "2_2") (pintype "passive"))
      (node (ref "U$2") (pin "3") (pinfunction "FB_3") (pintype "bidirectional"))
    )
    (net (code "63") (name "Net-(U$2-SW)") (class "Default")
      (node (ref "L1") (pin "1") (pinfunction "1_1") (pintype "passive"))
      (node (ref "U$2") (pin "7") (pinfunction "SW_7") (pintype "bidirectional"))
    )
    (net (code "64") (name "VCC") (class "Default")
      (node (ref "C10") (pin "1") (pinfunction "1_1") (pintype "passive"))
      (node (ref "C18") (pin "+") (pinfunction "+_+") (pintype "passive"))
      (node (ref "C20") (pin "1") (pinfunction "1_1") (pintype "passive"))
      (node (ref "C9") (pin "+") (pinfunction "+_+") (pintype "passive"))
      (node (ref "IC2") (pin "13") (pinfunction "VM2_13") (pintype "bidirectional"))
      (node (ref "IC2") (pin "14") (pinfunction "VM3_14") (pintype "bidirectional"))
      (node (ref "IC2") (pin "24") (pinfunction "VM1_24") (pintype "bidirectional"))
      (node (ref "R6") (pin "2") (pinfunction "2_2") (pintype "passive"))
      (node (ref "SW_POWER") (pin "3") (pinfunction "3_3") (pintype "passive"))
      (node (ref "U$2") (pin "1") (pinfunction "V_IN_A_1") (pintype "bidirectional"))
      (node (ref "U$2") (pin "2") (pinfunction "EN_2") (pintype "bidirectional"))
      (node (ref "U$2") (pin "6") (pinfunction "V_IN_SW_6") (pintype "bidirectional"))
    )
    (net (code "65") (name "VIN") (class "Default")
      (node (ref "BAT") (pin "1") (pinfunction "1_1") (pintype "passive"))
      (node (ref "SW_POWER") (pin "2") (pinfunction "2_2") (pintype "passive"))
    )
    (net (code "66") (name "unconnected-(IC1-CD+-Pad9)") (class "Default")
      (node (ref "IC1") (pin "9") (pinfunction "CD+_9") (pintype "passive"))
    )
    (net (code "67") (name "unconnected-(IMU-Pad4)") (class "Default")
      (node (ref "IMU") (pin "4") (pinfunction "4_4") (pintype "passive"))
    )
    (net (code "68") (name "unconnected-(STM1A-PA08-Pad41)") (class "Default")
      (node (ref "STM1") (pin "41") (pinfunction "PA08_41") (pintype "bidirectional"))
    )
    (net (code "69") (name "unconnected-(STM1A-PA11-Pad44)") (class "Default")
      (node (ref "STM1") (pin "44") (pinfunction "PA11_44") (pintype "bidirectional"))
    )
    (net (code "70") (name "unconnected-(STM1A-PA12-Pad45)") (class "Default")
      (node (ref "STM1") (pin "45") (pinfunction "PA12_45") (pintype "bidirectional"))
    )
    (net (code "71") (name "unconnected-(STM1A-PA15-Pad50)") (class "Default")
      (node (ref "STM1") (pin "50") (pinfunction "PA15_50") (pintype "bidirectional"))
    )
    (net (code "72") (name "unconnected-(STM1C-PB10-Pad29)") (class "Default")
      (node (ref "STM1") (pin "29") (pinfunction "PB10_29") (pintype "bidirectional"))
    )
    (net (code "73") (name "unconnected-(STM1C-PB12-Pad33)") (class "Default")
      (node (ref "STM1") (pin "33") (pinfunction "PB12_33") (pintype "bidirectional"))
    )
    (net (code "74") (name "unconnected-(STM1C-PB13-Pad34)") (class "Default")
      (node (ref "STM1") (pin "34") (pinfunction "PB13_34") (pintype "bidirectional"))
    )
    (net (code "75") (name "unconnected-(STM1C-PB14-Pad35)") (class "Default")
      (node (ref "STM1") (pin "35") (pinfunction "PB14_35") (pintype "bidirectional"))
    )
    (net (code "76") (name "unconnected-(STM1C-PB15-Pad36)") (class "Default")
      (node (ref "STM1") (pin "36") (pinfunction "PB15_36") (pintype "bidirectional"))
    )
    (net (code "77") (name "unconnected-(STM1D-PB03-Pad55)") (class "Default")
      (node (ref "STM1") (pin "55") (pinfunction "PB03_55") (pintype "bidirectional"))
    )
    (net (code "78") (name "unconnected-(STM1E-PC10-Pad51)") (class "Default")
      (node (ref "STM1") (pin "51") (pinfunction "PC10_51") (pintype "bidirectional"))
    )
    (net (code "79") (name "unconnected-(STM1E-PC11-Pad52)") (class "Default")
      (node (ref "STM1") (pin "52") (pinfunction "PC11_52") (pintype "bidirectional"))
    )
    (net (code "80") (name "unconnected-(STM1E-PC13-Pad2)") (class "Default")
      (node (ref "STM1") (pin "2") (pinfunction "PC13_2") (pintype "bidirectional"))
    )
    (net (code "81") (name "unconnected-(STM1E-PC14-Pad3)") (class "Default")
      (node (ref "STM1") (pin "3") (pinfunction "PC14_3") (pintype "bidirectional"))
    )
    (net (code "82") (name "unconnected-(STM1E-PC15-Pad4)") (class "Default")
      (node (ref "STM1") (pin "4") (pinfunction "PC15_4") (pintype "bidirectional"))
    )
    (net (code "83") (name "unconnected-(STM1G-PD2-Pad54)") (class "Default")
      (node (ref "STM1") (pin "54") (pinfunction "PD2_54") (pintype "bidirectional"))
    )
    (net (code "84") (name "unconnected-(SW_POWER-Pad1)") (class "Default")
      (node (ref "SW_POWER") (pin "1") (pinfunction "1_1") (pintype "passive"))
    )
  )
)
